# processor.net
KiCad netlist of a schematic drawn in Altium Designer
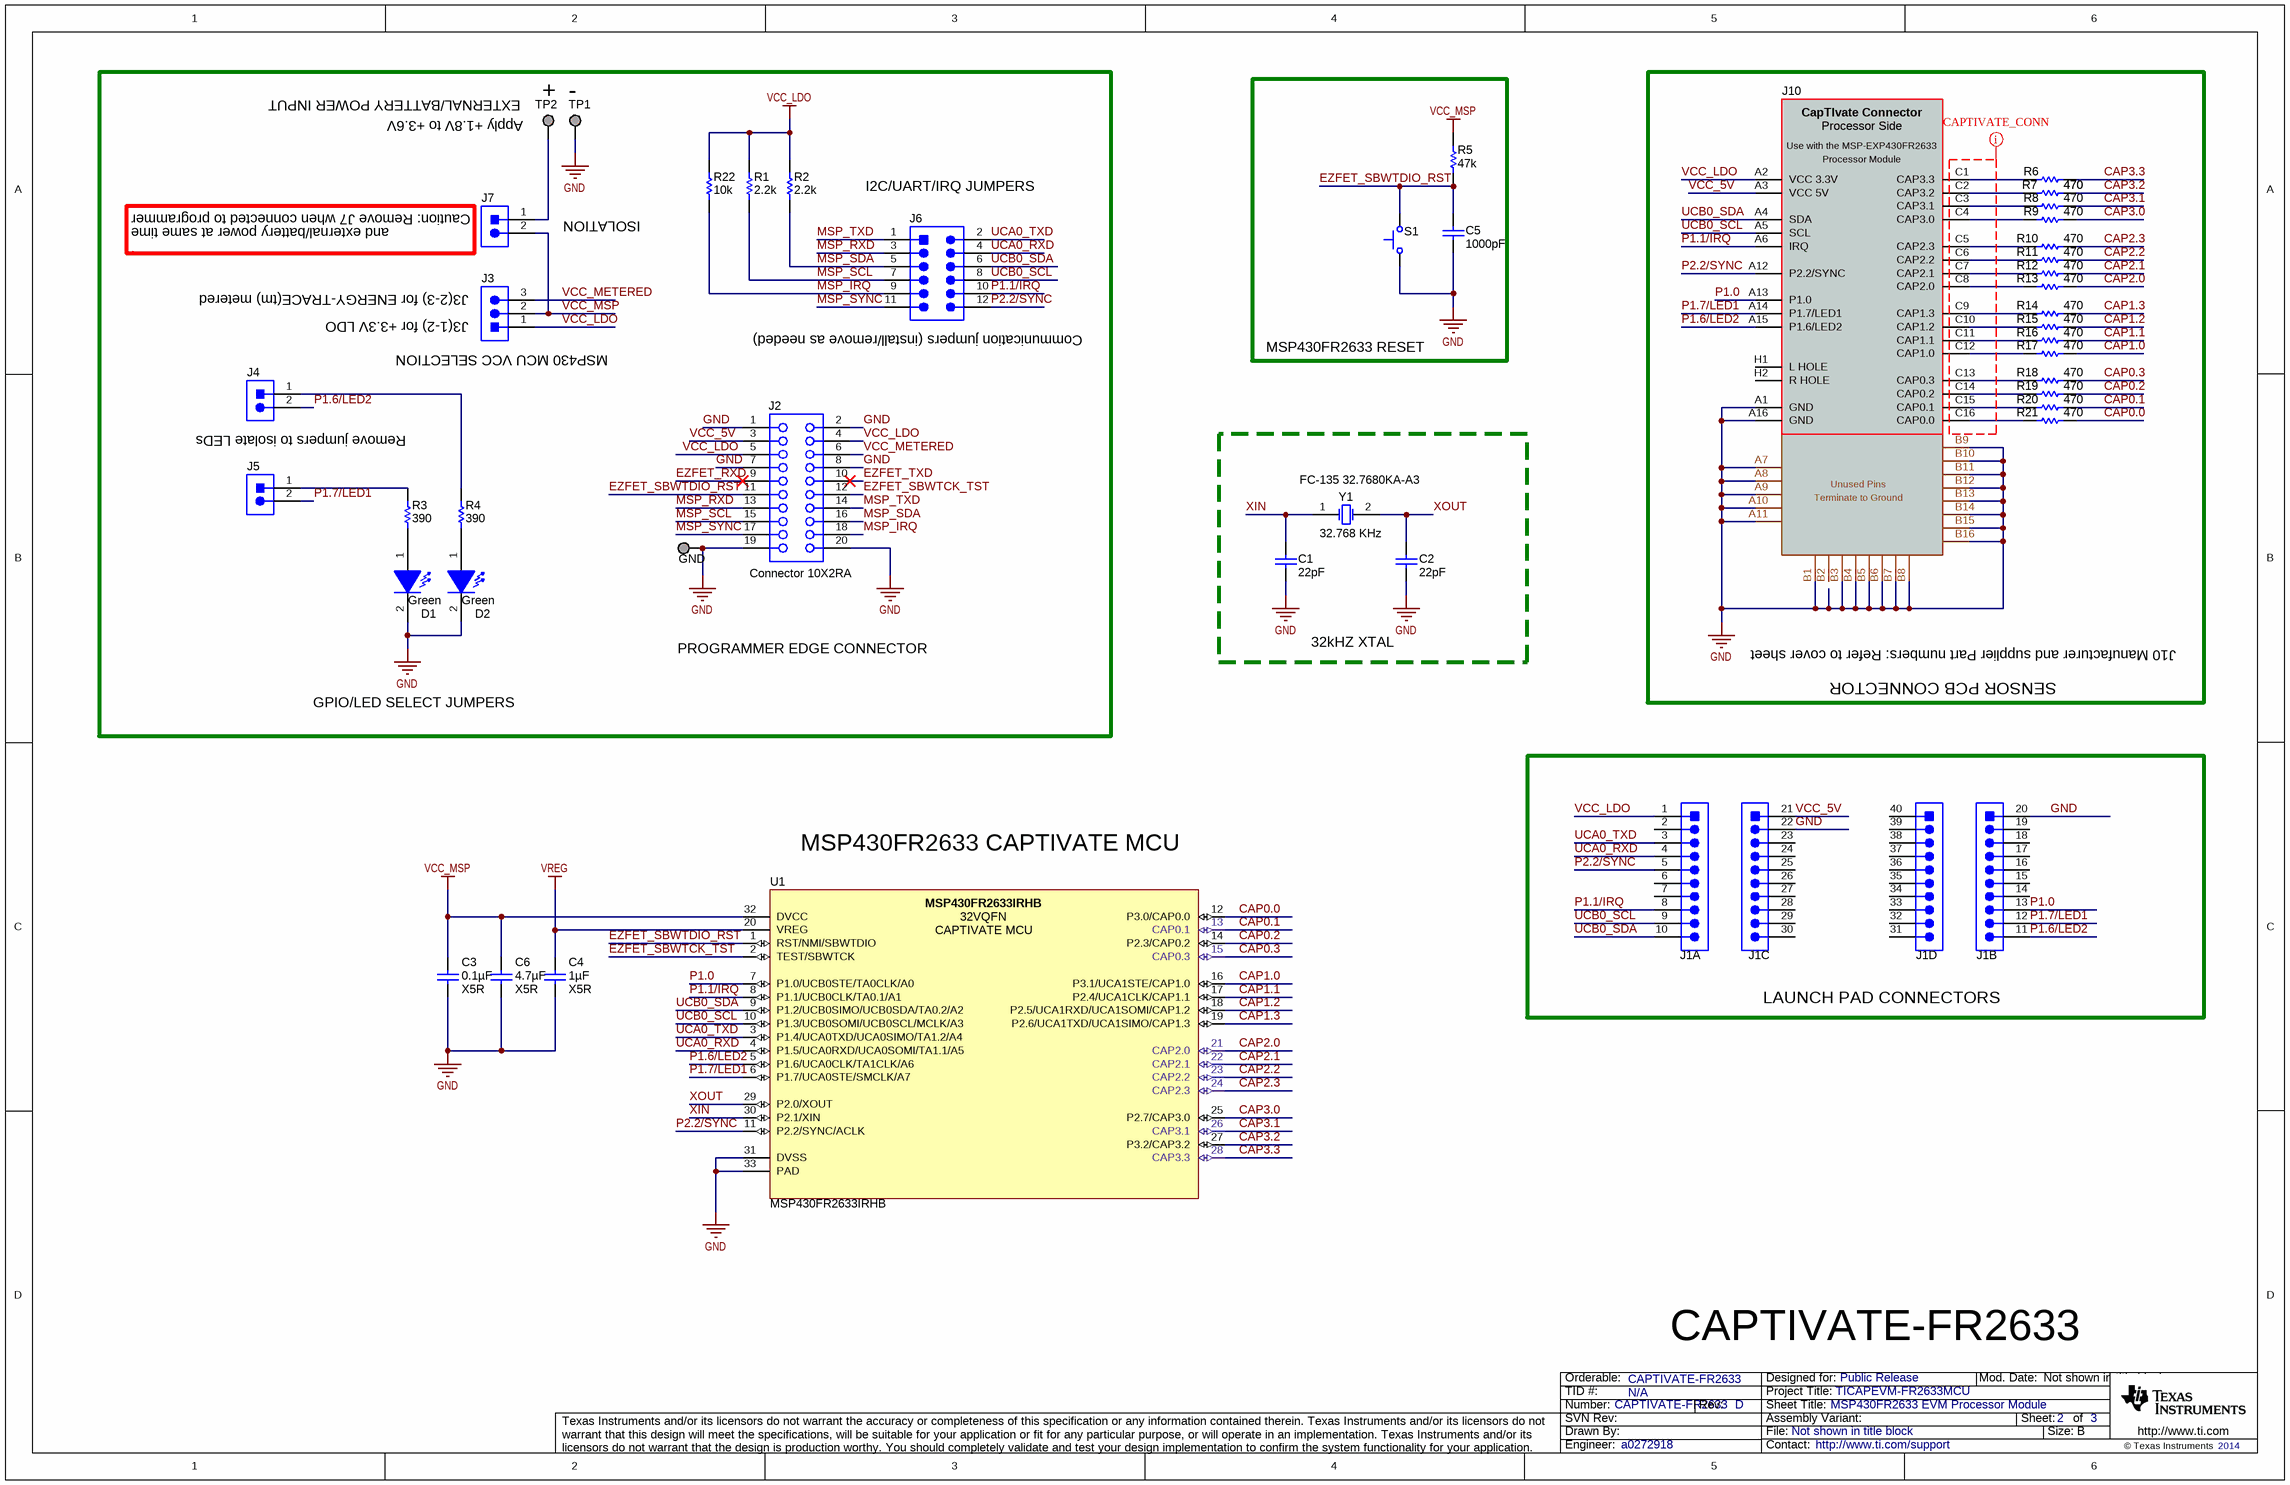
[diagram p0: processor.SchDoc]

(export (version "E")
  (design (tool "Eeschema 10.0.6"))
  (components
    (comp (ref "C1")
      (value "GRM1555C1H220JA01D")
      (footprint "0402")
      (description "CAP, CERM, 22 pF, 50 V, +/- 5%, C0G/NP0, 0402")
      (fields
        (field (name "VALUEDISPLAYED") "22pF")
        (field (name "MANUFACTURER") "MuRata")
        (field (name "PUBLISHER") "Texas Instruments")
      )
      (libsource (lib "Capacitor_Ceramic") (part "GRM1555C1H220JA01D"))
    )
    (comp (ref "C2")
      (value "GRM1555C1H220JA01D")
      (footprint "0402")
      (description "CAP, CERM, 22 pF, 50 V, +/- 5%, C0G/NP0, 0402")
      (fields
        (field (name "VALUEDISPLAYED") "22pF")
        (field (name "MANUFACTURER") "MuRata")
        (field (name "PUBLISHER") "Texas Instruments")
      )
      (libsource (lib "Capacitor_Ceramic") (part "GRM1555C1H220JA01D"))
    )
    (comp (ref "C3")
      (value "C1005X5R1A104K")
      (footprint "0402")
      (description "CAP, CERM, 0.1uF, 10V, +/-10%, X5R, 0402")
      (fields
        (field (name "VALUEDISPLAYED") "0.1µF")
        (field (name "MANUFACTURER") "TDK")
        (field (name "TEMPCO") "X5R")
        (field (name "PUBLISHER") "Texas Instruments")
      )
      (libsource (lib "Capacitor_Ceramic") (part "C1005X5R1A104K"))
    )
    (comp (ref "C4")
      (value "C1608X5R1A105K")
      (footprint "0603")
      (description "CAP, CERM, 1 µF, 10 V, +/- 10%, X5R, 0603")
      (fields
        (field (name "VALUEDISPLAYED") "1µF")
        (field (name "MANUFACTURER") "TDK")
        (field (name "TEMPCO") "X5R")
        (field (name "PUBLISHER") "Texas Instruments")
      )
      (libsource (lib "Capacitor_Ceramic") (part "C1608X5R1A105K"))
    )
    (comp (ref "C5")
      (value "C1005X7R1H102K")
      (footprint "0402")
      (description "CAP, CERM, 1000pF, 50V, +/-10%, X7R, 0402")
      (fields
        (field (name "VALUEDISPLAYED") "1000pF")
        (field (name "MANUFACTURER") "TDK")
        (field (name "PUBLISHER") "Texas Instruments")
      )
      (libsource (lib "Capacitor_Ceramic") (part "C1005X7R1H102K"))
    )
    (comp (ref "C6")
      (value "CGB3B1X5R1A475K055AC")
      (footprint "0603")
      (description "CAP, CERM, 4.7 µF, 10 V, +/- 10%, X5R, 0603")
      (fields
        (field (name "VALUEDISPLAYED") "4.7µF")
        (field (name "MANUFACTURER") "TDK")
        (field (name "TEMPCO") "X5R")
        (field (name "PUBLISHER") "Texas Instruments")
      )
      (libsource (lib "Capacitor_Ceramic") (part "CGB3B1X5R1A475K055AC"))
    )
    (comp (ref "D1")
      (value "Green")
      (footprint "LED_LTST-C190")
      (description "LED, Green, SMD")
      (fields
        (field (name "MANUFACTURER") "Lite-On")
        (field (name "PARTNUMBER") "LTST-C190GKT")
        (field (name "PUBLISHER") "Texas Instruments")
      )
      (libsource (lib "LED") (part "LTST-C190GKT"))
    )
    (comp (ref "D2")
      (value "Green")
      (footprint "LED_LTST-C190")
      (description "LED, Green, SMD")
      (fields
        (field (name "MANUFACTURER") "Lite-On")
        (field (name "PARTNUMBER") "LTST-C190GKT")
        (field (name "PUBLISHER") "Texas Instruments")
      )
      (libsource (lib "LED") (part "LTST-C190GKT"))
    )
    (comp (ref "GND")
      (value "TESTPOINT")
      (footprint "TP_VIA_060RND040")
      (description "TEST POINT.  No entry in BOM.")
      (fields (field (name "PUBLISHER") "Texas Instruments"))
      (libsource (lib "MiscParts") (part "TESTPOINT"))
    )
    (comp (ref "J1")
      (value "TSW-110-07-G-S")
      (footprint "40Pin BP")
      (description "Header, 100mil, 10x1, Gold, TH")
      (fields
        (field (name "MANUFACTURER") "Samtec")
        (field (name "SYMBOLCREATOR") "a0412235")
        (field (name "PUBLISHER") "Texas Instruments")
      )
      (libsource (lib "Captivate Library") (part "BoosterPack Connector"))
    )
    (comp (ref "J2")
      (value "Connector 10X2RA")
      (footprint "CONN2X10RA")
      (description "Connector, Female, 10-Pin, 2 row, Right Angle")
      (fields
        (field (name "MANUFACTURER") "Samtec")
        (field (name "PARTNUMBER") "SSW-110-22-F-D-RA")
        (field (name "PUBLISHER") "Altium Limited")
      )
      (libsource (lib "Captivate Library") (part "Connector 10X2RA"))
    )
    (comp (ref "J3")
      (value "HTSW-103-07-G-S")
      (footprint "Samtec_HTSW-103-07-G-S")
      (description "Header, 100mil, 3x1, Gold, TH")
      (fields
        (field (name "MANUFACTURER") "Samtec")
        (field (name "SYMBOLCREATOR") "a0799628")
        (field (name "PUBLISHER") "Texas Instruments")
      )
      (libsource (lib "Connectors_Samtec") (part "HTSW-103-07-G-S"))
    )
    (comp (ref "J4")
      (value "HTSW-102-07-G-S")
      (footprint "Samtec_HTSW-102-07-G-S")
      (description "Header, 100mil, 2x1, Gold, TH")
      (fields
        (field (name "MANUFACTURER") "Samtec")
        (field (name "SYMBOLCREATOR") "a0412235")
        (field (name "PUBLISHER") "Texas Instruments")
      )
      (libsource (lib "Connectors_Samtec") (part "HTSW-102-07-G-S"))
    )
    (comp (ref "J5")
      (value "HTSW-102-07-G-S")
      (footprint "Samtec_HTSW-102-07-G-S")
      (description "Header, 100mil, 2x1, Gold, TH")
      (fields
        (field (name "MANUFACTURER") "Samtec")
        (field (name "SYMBOLCREATOR") "a0412235")
        (field (name "PUBLISHER") "Texas Instruments")
      )
      (libsource (lib "Connectors_Samtec") (part "HTSW-102-07-G-S"))
    )
    (comp (ref "J6")
      (value "TSW-106-07-G-D")
      (footprint "TSW-106-07-G-D")
      (description "Header, 100mil, 6x2, Gold, TH")
      (fields
        (field (name "MANUFACTURER") "Samtec")
        (field (name "SYMBOLCREATOR") "a0412235")
        (field (name "PUBLISHER") "Texas Instruments")
      )
      (libsource (lib "Connectors") (part "TSW-106-07-G-D"))
    )
    (comp (ref "J7")
      (value "HTSW-102-07-G-S")
      (footprint "Samtec_HTSW-102-07-G-S")
      (description "Header, 100mil, 2x1, Gold, TH")
      (fields
        (field (name "MANUFACTURER") "Samtec")
        (field (name "SYMBOLCREATOR") "a0412235")
        (field (name "PUBLISHER") "Texas Instruments")
      )
      (libsource (lib "Connectors_Samtec") (part "HTSW-102-07-G-S"))
    )
    (comp (ref "J10")
      (value "09 28 248 6921")
      (footprint "CAPTIVATE-CONN-48-NONUM")
      (description "CapTIvate Processor-Side Connector, 3x16, 100mil, TH, RA, F, MSP-EXP430FR2633")
      (fields
        (field (name "MANUFACTURER") "Harting")
        (field (name "ALTERNATE PARTNUMBER") "5650868-4")
        (field (name "SYMBOLCREATOR") "Use a-id")
      )
      (libsource (lib "CapTIvate_Connector") (part "CAPTIVATE-CONN-MSP-EXP430FR2633-PROC"))
    )
    (comp (ref "R1")
      (value "CRCW04022K20JNED")
      (footprint "0402")
      (description "RES, 2.2 k, 5%, 0.063 W, 0402")
      (fields
        (field (name "MANUFACTURER") "Vishay-Dale")
        (field (name "VALUEDISPLAYED") "2.2k")
        (field (name "PUBLISHER") "Texas Instruments")
      )
      (libsource (lib "Resistor_0402") (part "CRCW04022K20JNED"))
    )
    (comp (ref "R2")
      (value "CRCW04022K20JNED")
      (footprint "0402")
      (description "RES, 2.2 k, 5%, 0.063 W, 0402")
      (fields
        (field (name "MANUFACTURER") "Vishay-Dale")
        (field (name "VALUEDISPLAYED") "2.2k")
        (field (name "PUBLISHER") "Texas Instruments")
      )
      (libsource (lib "Resistor_0402") (part "CRCW04022K20JNED"))
    )
    (comp (ref "R3")
      (value "390")
      (footprint "0402")
      (description "RES, 390 ohm, 5%, 0.063W, 0402")
      (fields
        (field (name "PARTNUMBER") "CRCW0402390RJNED")
        (field (name "MANUFACTURER") "Vishay-Dale")
        (field (name "PUBLISHER") "Texas Instruments")
      )
      (libsource (lib "Resistor_0402") (part "CRCW0402390RJNED"))
    )
    (comp (ref "R4")
      (value "390")
      (footprint "0402")
      (description "RES, 390 ohm, 5%, 0.063W, 0402")
      (fields
        (field (name "PARTNUMBER") "CRCW0402390RJNED")
        (field (name "MANUFACTURER") "Vishay-Dale")
        (field (name "PUBLISHER") "Texas Instruments")
      )
      (libsource (lib "Resistor_0402") (part "CRCW0402390RJNED"))
    )
    (comp (ref "R5")
      (value "47k")
      (footprint "0402")
      (description "RES, 47k ohm, 5%, 0.063W, 0402")
      (fields
        (field (name "PARTNUMBER") "CRCW040247K0JNED")
        (field (name "MANUFACTURER") "Vishay-Dale")
        (field (name "PUBLISHER") "Texas Instruments")
      )
      (libsource (lib "Resistor_0402") (part "CRCW040247K0JNED"))
    )
    (comp (ref "R6")
      (value "CRCW0402470RJNED")
      (footprint "0402")
      (description "RES, 470, 5%, 0.063 W, 0402")
      (fields
        (field (name "MANUFACTURER") "Vishay-Dale")
        (field (name "VALUEDISPLAYED") "470")
        (field (name "PUBLISHER") "Texas Instruments")
      )
      (libsource (lib "Resistor_0402") (part "CRCW0402470RJNED"))
    )
    (comp (ref "R7")
      (value "CRCW0402470RJNED")
      (footprint "0402")
      (description "RES, 470, 5%, 0.063 W, 0402")
      (fields
        (field (name "MANUFACTURER") "Vishay-Dale")
        (field (name "VALUEDISPLAYED") "470")
        (field (name "PUBLISHER") "Texas Instruments")
      )
      (libsource (lib "Resistor_0402") (part "CRCW0402470RJNED"))
    )
    (comp (ref "R8")
      (value "CRCW0402470RJNED")
      (footprint "0402")
      (description "RES, 470, 5%, 0.063 W, 0402")
      (fields
        (field (name "MANUFACTURER") "Vishay-Dale")
        (field (name "VALUEDISPLAYED") "470")
        (field (name "PUBLISHER") "Texas Instruments")
      )
      (libsource (lib "Resistor_0402") (part "CRCW0402470RJNED"))
    )
    (comp (ref "R9")
      (value "CRCW0402470RJNED")
      (footprint "0402")
      (description "RES, 470, 5%, 0.063 W, 0402")
      (fields
        (field (name "MANUFACTURER") "Vishay-Dale")
        (field (name "VALUEDISPLAYED") "470")
        (field (name "PUBLISHER") "Texas Instruments")
      )
      (libsource (lib "Resistor_0402") (part "CRCW0402470RJNED"))
    )
    (comp (ref "R10")
      (value "CRCW0402470RJNED")
      (footprint "0402")
      (description "RES, 470, 5%, 0.063 W, 0402")
      (fields
        (field (name "MANUFACTURER") "Vishay-Dale")
        (field (name "VALUEDISPLAYED") "470")
        (field (name "PUBLISHER") "Texas Instruments")
      )
      (libsource (lib "Resistor_0402") (part "CRCW0402470RJNED"))
    )
    (comp (ref "R11")
      (value "CRCW0402470RJNED")
      (footprint "0402")
      (description "RES, 470, 5%, 0.063 W, 0402")
      (fields
        (field (name "MANUFACTURER") "Vishay-Dale")
        (field (name "VALUEDISPLAYED") "470")
        (field (name "PUBLISHER") "Texas Instruments")
      )
      (libsource (lib "Resistor_0402") (part "CRCW0402470RJNED"))
    )
    (comp (ref "R12")
      (value "CRCW0402470RJNED")
      (footprint "0402")
      (description "RES, 470, 5%, 0.063 W, 0402")
      (fields
        (field (name "MANUFACTURER") "Vishay-Dale")
        (field (name "VALUEDISPLAYED") "470")
        (field (name "PUBLISHER") "Texas Instruments")
      )
      (libsource (lib "Resistor_0402") (part "CRCW0402470RJNED"))
    )
    (comp (ref "R13")
      (value "CRCW0402470RJNED")
      (footprint "0402")
      (description "RES, 470, 5%, 0.063 W, 0402")
      (fields
        (field (name "MANUFACTURER") "Vishay-Dale")
        (field (name "VALUEDISPLAYED") "470")
        (field (name "PUBLISHER") "Texas Instruments")
      )
      (libsource (lib "Resistor_0402") (part "CRCW0402470RJNED"))
    )
    (comp (ref "R14")
      (value "CRCW0402470RJNED")
      (footprint "0402")
      (description "RES, 470, 5%, 0.063 W, 0402")
      (fields
        (field (name "MANUFACTURER") "Vishay-Dale")
        (field (name "VALUEDISPLAYED") "470")
        (field (name "PUBLISHER") "Texas Instruments")
      )
      (libsource (lib "Resistor_0402") (part "CRCW0402470RJNED"))
    )
    (comp (ref "R15")
      (value "CRCW0402470RJNED")
      (footprint "0402")
      (description "RES, 470, 5%, 0.063 W, 0402")
      (fields
        (field (name "MANUFACTURER") "Vishay-Dale")
        (field (name "VALUEDISPLAYED") "470")
        (field (name "PUBLISHER") "Texas Instruments")
      )
      (libsource (lib "Resistor_0402") (part "CRCW0402470RJNED"))
    )
    (comp (ref "R16")
      (value "CRCW0402470RJNED")
      (footprint "0402")
      (description "RES, 470, 5%, 0.063 W, 0402")
      (fields
        (field (name "MANUFACTURER") "Vishay-Dale")
        (field (name "VALUEDISPLAYED") "470")
        (field (name "PUBLISHER") "Texas Instruments")
      )
      (libsource (lib "Resistor_0402") (part "CRCW0402470RJNED"))
    )
    (comp (ref "R17")
      (value "CRCW0402470RJNED")
      (footprint "0402")
      (description "RES, 470, 5%, 0.063 W, 0402")
      (fields
        (field (name "MANUFACTURER") "Vishay-Dale")
        (field (name "VALUEDISPLAYED") "470")
        (field (name "PUBLISHER") "Texas Instruments")
      )
      (libsource (lib "Resistor_0402") (part "CRCW0402470RJNED"))
    )
    (comp (ref "R18")
      (value "CRCW0402470RJNED")
      (footprint "0402")
      (description "RES, 470, 5%, 0.063 W, 0402")
      (fields
        (field (name "MANUFACTURER") "Vishay-Dale")
        (field (name "VALUEDISPLAYED") "470")
        (field (name "PUBLISHER") "Texas Instruments")
      )
      (libsource (lib "Resistor_0402") (part "CRCW0402470RJNED"))
    )
    (comp (ref "R19")
      (value "CRCW0402470RJNED")
      (footprint "0402")
      (description "RES, 470, 5%, 0.063 W, 0402")
      (fields
        (field (name "MANUFACTURER") "Vishay-Dale")
        (field (name "VALUEDISPLAYED") "470")
        (field (name "PUBLISHER") "Texas Instruments")
      )
      (libsource (lib "Resistor_0402") (part "CRCW0402470RJNED"))
    )
    (comp (ref "R20")
      (value "CRCW0402470RJNED")
      (footprint "0402")
      (description "RES, 470, 5%, 0.063 W, 0402")
      (fields
        (field (name "MANUFACTURER") "Vishay-Dale")
        (field (name "VALUEDISPLAYED") "470")
        (field (name "PUBLISHER") "Texas Instruments")
      )
      (libsource (lib "Resistor_0402") (part "CRCW0402470RJNED"))
    )
    (comp (ref "R21")
      (value "CRCW0402470RJNED")
      (footprint "0402")
      (description "RES, 470, 5%, 0.063 W, 0402")
      (fields
        (field (name "MANUFACTURER") "Vishay-Dale")
        (field (name "VALUEDISPLAYED") "470")
        (field (name "PUBLISHER") "Texas Instruments")
      )
      (libsource (lib "Resistor_0402") (part "CRCW0402470RJNED"))
    )
    (comp (ref "R22")
      (value "CRCW040210K0JNED")
      (footprint "0402")
      (description "RES, 10 k, 5%, 0.063 W, 0402")
      (fields
        (field (name "MANUFACTURER") "Vishay-Dale")
        (field (name "VALUEDISPLAYED") "10k")
        (field (name "PUBLISHER") "Texas Instruments")
      )
      (libsource (lib "Resistor_0402") (part "CRCW040210K0JNED"))
    )
    (comp (ref "S1")
      (value "EVQ-21505R")
      (footprint "SW_EVQ-21x05")
      (description "Switch, Tactile, SPST-NO, 0.02A, 15V, TH")
      (fields (field (name "MANUFACTURER") "Panasonic") (field (name "PUBLISHER") "Texas Instruments"))
      (libsource (lib "Switches") (part "EVQ-21505R"))
    )
    (comp (ref "TP1")
      (value "-")
      (footprint "TESTPOINT")
      (description "TEST POINT.  No entry in BOM.")
      (fields (field (name "PUBLISHER") "Texas Instruments"))
      (libsource (lib "MiscParts") (part "TESTPOINT"))
    )
    (comp (ref "TP2")
      (value "+")
      (footprint "TESTPOINT")
      (description "TEST POINT.  No entry in BOM.")
      (fields (field (name "PUBLISHER") "Texas Instruments"))
      (libsource (lib "MiscParts") (part "TESTPOINT"))
    )
    (comp (ref "U1")
      (value "MSP430FR2633IRHB")
      (footprint "RHB0032E")
      (description "MSP430 Captivate Microcontroller")
      (fields (field (name "MANUFACTURER") "Texas Instruments") (field (name "SYMBOLCREATOR") "W. Schnoor"))
      (libsource (lib "Captivate Library") (part "MSP430FR2633IRHB"))
    )
    (comp (ref "Y1")
      (value "FC-135 32.7680KA-A3")
      (footprint "Epson_FC-135")
      (description "Crystal, 32.768 KHz, 12.5 pF, SMD")
      (fields
        (field (name "FREQUENCY") "32.768 KHz")
        (field (name "MANUFACTURER") "Epson")
        (field (name "SYMBOLCREATOR") "a0412235")
        (field (name "PUBLISHER") "Texas Instruments")
      )
      (libsource (lib "Oscillators") (part "FC-135 32.7680KA-A3"))
    )
  )
  (nets
    (net (code "1") (name "/CAP0.0") (class "Default")
      (node (ref "R21") (pin "2") (pinfunction "2_2") (pintype "passive"))
      (node (ref "U1") (pin "12") (pinfunction "P3.0/CAP0.0_12") (pintype "bidirectional"))
    )
    (net (code "2") (name "/CAP0.1") (class "Default")
      (node (ref "R20") (pin "2") (pinfunction "2_2") (pintype "passive"))
      (node (ref "U1") (pin "13") (pinfunction "CAP0.1_13") (pintype "bidirectional"))
    )
    (net (code "3") (name "/CAP0.2") (class "Default")
      (node (ref "R19") (pin "2") (pinfunction "2_2") (pintype "passive"))
      (node (ref "U1") (pin "14") (pinfunction "P2.3/CAP0.2_14") (pintype "bidirectional"))
    )
    (net (code "4") (name "/CAP0.3") (class "Default")
      (node (ref "R18") (pin "2") (pinfunction "2_2") (pintype "passive"))
      (node (ref "U1") (pin "15") (pinfunction "CAP0.3_15") (pintype "bidirectional"))
    )
    (net (code "5") (name "/CAP1.0") (class "Default")
      (node (ref "R17") (pin "2") (pinfunction "2_2") (pintype "passive"))
      (node (ref "U1") (pin "16") (pinfunction "P3.1/UCA1STE/CAP1.0_16") (pintype "bidirectional"))
    )
    (net (code "6") (name "/CAP1.1") (class "Default")
      (node (ref "R16") (pin "2") (pinfunction "2_2") (pintype "passive"))
      (node (ref "U1") (pin "17") (pinfunction "P2.4/UCA1CLK/CAP1.1_17") (pintype "bidirectional"))
    )
    (net (code "7") (name "/CAP1.2") (class "Default")
      (node (ref "R15") (pin "2") (pinfunction "2_2") (pintype "passive"))
      (node (ref "U1") (pin "18") (pinfunction "P2.5/UCA1RXD/UCA1SOMI/CAP1.2_18") (pintype "bidirectional"))
    )
    (net (code "8") (name "/CAP1.3") (class "Default")
      (node (ref "R14") (pin "2") (pinfunction "2_2") (pintype "passive"))
      (node (ref "U1") (pin "19") (pinfunction "P2.6/UCA1TXD/UCA1SIMO/CAP1.3_19") (pintype "bidirectional"))
    )
    (net (code "9") (name "/CAP2.0") (class "Default")
      (node (ref "R13") (pin "2") (pinfunction "2_2") (pintype "passive"))
      (node (ref "U1") (pin "21") (pinfunction "CAP2.0_21") (pintype "bidirectional"))
    )
    (net (code "10") (name "/CAP2.1") (class "Default")
      (node (ref "R12") (pin "2") (pinfunction "2_2") (pintype "passive"))
      (node (ref "U1") (pin "22") (pinfunction "CAP2.1_22") (pintype "bidirectional"))
    )
    (net (code "11") (name "/CAP2.2") (class "Default")
      (node (ref "R11") (pin "2") (pinfunction "2_2") (pintype "passive"))
      (node (ref "U1") (pin "23") (pinfunction "CAP2.2_23") (pintype "bidirectional"))
    )
    (net (code "12") (name "/CAP2.3") (class "Default")
      (node (ref "R10") (pin "2") (pinfunction "2_2") (pintype "passive"))
      (node (ref "U1") (pin "24") (pinfunction "CAP2.3_24") (pintype "bidirectional"))
    )
    (net (code "13") (name "/CAP3.0") (class "Default")
      (node (ref "R9") (pin "2") (pinfunction "2_2") (pintype "passive"))
      (node (ref "U1") (pin "25") (pinfunction "P2.7/CAP3.0_25") (pintype "bidirectional"))
    )
    (net (code "14") (name "/CAP3.1") (class "Default")
      (node (ref "R8") (pin "2") (pinfunction "2_2") (pintype "passive"))
      (node (ref "U1") (pin "26") (pinfunction "CAP3.1_26") (pintype "bidirectional"))
    )
    (net (code "15") (name "/CAP3.2") (class "Default")
      (node (ref "R7") (pin "2") (pinfunction "2_2") (pintype "passive"))
      (node (ref "U1") (pin "27") (pinfunction "P3.2/CAP3.2_27") (pintype "bidirectional"))
    )
    (net (code "16") (name "/CAP3.3") (class "Default")
      (node (ref "R6") (pin "2") (pinfunction "2_2") (pintype "passive"))
      (node (ref "U1") (pin "28") (pinfunction "CAP3.3_28") (pintype "bidirectional"))
    )
    (net (code "17") (name "/EZFET_RXD") (class "Default")
      (node (ref "J2") (pin "9") (pinfunction "9_9") (pintype "passive+no_connect"))
    )
    (net (code "18") (name "/EZFET_SBWTCK_TST") (class "Default")
      (node (ref "J2") (pin "12") (pinfunction "12_12") (pintype "passive"))
      (node (ref "U1") (pin "2") (pinfunction "TEST/SBWTCK_2") (pintype "bidirectional"))
    )
    (net (code "19") (name "/EZFET_SBWTDIO_RST") (class "Default")
      (node (ref "C5") (pin "1") (pinfunction "1_1") (pintype "passive"))
      (node (ref "J2") (pin "11") (pinfunction "11_11") (pintype "passive"))
      (node (ref "R5") (pin "1") (pinfunction "1_1") (pintype "passive"))
      (node (ref "S1") (pin "2") (pinfunction "2_2") (pintype "passive"))
      (node (ref "U1") (pin "1") (pinfunction "RST/NMI/SBWTDIO_1") (pintype "bidirectional"))
    )
    (net (code "20") (name "/EZFET_TXD") (class "Default")
      (node (ref "J2") (pin "10") (pinfunction "10_10") (pintype "passive+no_connect"))
    )
    (net (code "21") (name "/MSP_IRQ") (class "Default")
      (node (ref "J2") (pin "18") (pinfunction "18_18") (pintype "passive"))
      (node (ref "J6") (pin "9") (pinfunction "9_9") (pintype "passive"))
      (node (ref "R22") (pin "1") (pinfunction "1_1") (pintype "passive"))
    )
    (net (code "22") (name "/MSP_RXD") (class "Default")
      (node (ref "J2") (pin "13") (pinfunction "13_13") (pintype "passive"))
      (node (ref "J6") (pin "3") (pinfunction "3_3") (pintype "passive"))
    )
    (net (code "23") (name "/MSP_SCL") (class "Default")
      (node (ref "J2") (pin "15") (pinfunction "15_15") (pintype "passive"))
      (node (ref "J6") (pin "7") (pinfunction "7_7") (pintype "passive"))
      (node (ref "R1") (pin "1") (pinfunction "1_1") (pintype "passive"))
    )
    (net (code "24") (name "/MSP_SDA") (class "Default")
      (node (ref "J2") (pin "16") (pinfunction "16_16") (pintype "passive"))
      (node (ref "J6") (pin "5") (pinfunction "5_5") (pintype "passive"))
      (node (ref "R2") (pin "1") (pinfunction "1_1") (pintype "passive"))
    )
    (net (code "25") (name "/MSP_SYNC") (class "Default")
      (node (ref "J2") (pin "17") (pinfunction "17_17") (pintype "passive"))
      (node (ref "J6") (pin "11") (pinfunction "11_11") (pintype "passive"))
    )
    (net (code "26") (name "/MSP_TXD") (class "Default")
      (node (ref "J2") (pin "14") (pinfunction "14_14") (pintype "passive"))
      (node (ref "J6") (pin "1") (pinfunction "1_1") (pintype "passive"))
    )
    (net (code "27") (name "/P1.0") (class "Default")
      (node (ref "J1") (pin "13") (pinfunction "13_13") (pintype "passive"))
      (node (ref "J10") (pin "A13") (pinfunction "P1.0_A13") (pintype "open_collector"))
      (node (ref "U1") (pin "7") (pinfunction "P1.0/UCB0STE/TA0CLK/A0_7") (pintype "bidirectional"))
    )
    (net (code "28") (name "/P1.1{slash}IRQ") (class "Default")
      (node (ref "J1") (pin "8") (pinfunction "8_8") (pintype "passive"))
      (node (ref "J10") (pin "A6") (pinfunction "IRQ_A6") (pintype "open_collector"))
      (node (ref "J6") (pin "10") (pinfunction "10_10") (pintype "passive"))
      (node (ref "U1") (pin "8") (pinfunction "P1.1/UCB0CLK/TA0.1/A1_8") (pintype "bidirectional"))
    )
    (net (code "29") (name "/P1.6{slash}LED2") (class "Default")
      (node (ref "J1") (pin "11") (pinfunction "11_11") (pintype "passive"))
      (node (ref "J10") (pin "A15") (pinfunction "P1.6/LED2_A15") (pintype "open_collector"))
      (node (ref "J4") (pin "2") (pinfunction "2_2") (pintype "passive"))
      (node (ref "U1") (pin "5") (pinfunction "P1.6/UCA0CLK/TA1CLK/A6_5") (pintype "bidirectional"))
    )
    (net (code "30") (name "/P1.7{slash}LED1") (class "Default")
      (node (ref "J1") (pin "12") (pinfunction "12_12") (pintype "passive"))
      (node (ref "J10") (pin "A14") (pinfunction "P1.7/LED1_A14") (pintype "open_collector"))
      (node (ref "J5") (pin "2") (pinfunction "2_2") (pintype "passive"))
      (node (ref "U1") (pin "6") (pinfunction "P1.7/UCA0STE/SMCLK/A7_6") (pintype "bidirectional"))
    )
    (net (code "31") (name "/P2.2{slash}SYNC") (class "Default")
      (node (ref "J1") (pin "5") (pinfunction "5_5") (pintype "passive"))
      (node (ref "J10") (pin "A12") (pinfunction "P2.2/SYNC_A12") (pintype "open_collector"))
      (node (ref "J6") (pin "12") (pinfunction "12_12") (pintype "passive"))
      (node (ref "U1") (pin "11") (pinfunction "P2.2/SYNC/ACLK_11") (pintype "bidirectional"))
    )
    (net (code "32") (name "/UCA0_RXD") (class "Default")
      (node (ref "J1") (pin "4") (pinfunction "4_4") (pintype "passive"))
      (node (ref "J6") (pin "4") (pinfunction "4_4") (pintype "passive"))
      (node (ref "U1") (pin "4") (pinfunction "P1.5/UCA0RXD/UCA0SOMI/TA1.1/A5_4") (pintype "bidirectional"))
    )
    (net (code "33") (name "/UCA0_TXD") (class "Default")
      (node (ref "J1") (pin "3") (pinfunction "3_3") (pintype "passive"))
      (node (ref "J6") (pin "2") (pinfunction "2_2") (pintype "passive"))
      (node (ref "U1") (pin "3") (pinfunction "P1.4/UCA0TXD/UCA0SIMO/TA1.2/A4_3") (pintype "bidirectional"))
    )
    (net (code "34") (name "/UCB0_SCL") (class "Default")
      (node (ref "J1") (pin "9") (pinfunction "9_9") (pintype "passive"))
      (node (ref "J10") (pin "A5") (pinfunction "SCL_A5") (pintype "open_collector"))
      (node (ref "J6") (pin "8") (pinfunction "8_8") (pintype "passive"))
      (node (ref "U1") (pin "10") (pinfunction "P1.3/UCB0SOMI/UCB0SCL/MCLK/A3_10") (pintype "bidirectional"))
    )
    (net (code "35") (name "/UCB0_SDA") (class "Default")
      (node (ref "J1") (pin "10") (pinfunction "10_10") (pintype "passive"))
      (node (ref "J10") (pin "A4") (pinfunction "SDA_A4") (pintype "open_collector"))
      (node (ref "J6") (pin "6") (pinfunction "6_6") (pintype "passive"))
      (node (ref "U1") (pin "9") (pinfunction "P1.2/UCB0SIMO/UCB0SDA/TA0.2/A2_9") (pintype "bidirectional"))
    )
    (net (code "36") (name "/VCC_5V") (class "Default")
      (node (ref "J1") (pin "21") (pinfunction "21_21") (pintype "passive"))
      (node (ref "J10") (pin "A3") (pinfunction "VCC_5V_A3") (pintype "power_in"))
      (node (ref "J2") (pin "3") (pinfunction "3_3") (pintype "passive"))
    )
    (net (code "37") (name "/VCC_METERED") (class "Default")
      (node (ref "J2") (pin "6") (pinfunction "6_6") (pintype "passive"))
      (node (ref "J3") (pin "3") (pinfunction "3_3") (pintype "passive"))
    )
    (net (code "38") (name "/XIN") (class "Default")
      (node (ref "C1") (pin "1") (pinfunction "1_1") (pintype "passive"))
      (node (ref "U1") (pin "30") (pinfunction "P2.1/XIN_30") (pintype "bidirectional"))
      (node (ref "Y1") (pin "1") (pinfunction "OSC1_1") (pintype "passive"))
    )
    (net (code "39") (name "/XOUT") (class "Default")
      (node (ref "C2") (pin "1") (pinfunction "1_1") (pintype "passive"))
      (node (ref "U1") (pin "29") (pinfunction "P2.0/XOUT_29") (pintype "bidirectional"))
      (node (ref "Y1") (pin "2") (pinfunction "OSC2_2") (pintype "passive"))
    )
    (net (code "40") (name "GND") (class "Default")
      (node (ref "C1") (pin "2") (pinfunction "2_2") (pintype "passive"))
      (node (ref "C2") (pin "2") (pinfunction "2_2") (pintype "passive"))
      (node (ref "C3") (pin "2") (pinfunction "2_2") (pintype "passive"))
      (node (ref "C4") (pin "2") (pinfunction "2_2") (pintype "passive"))
      (node (ref "C5") (pin "2") (pinfunction "2_2") (pintype "passive"))
      (node (ref "C6") (pin "2") (pinfunction "2_2") (pintype "passive"))
      (node (ref "D1") (pin "2") (pinfunction "K_2") (pintype "passive"))
      (node (ref "D2") (pin "2") (pinfunction "K_2") (pintype "passive"))
      (node (ref "GND") (pin "1") (pintype "passive"))
      (node (ref "J1") (pin "20") (pinfunction "20_20") (pintype "passive"))
      (node (ref "J1") (pin "22") (pinfunction "22_22") (pintype "passive"))
      (node (ref "J10") (pin "A1") (pinfunction "GND_A1") (pintype "power_in"))
      (node (ref "J10") (pin "A10") (pinfunction "A10_A10") (pintype "passive"))
      (node (ref "J10") (pin "A11") (pinfunction "A11_A11") (pintype "passive"))
      (node (ref "J10") (pin "A16") (pinfunction "GND_A16") (pintype "power_in"))
      (node (ref "J10") (pin "A7") (pinfunction "A7_A7") (pintype "passive"))
      (node (ref "J10") (pin "A8") (pinfunction "A8_A8") (pintype "passive"))
      (node (ref "J10") (pin "A9") (pinfunction "A9_A9") (pintype "passive"))
      (node (ref "J10") (pin "B1") (pinfunction "B1_B1") (pintype "passive"))
      (node (ref "J10") (pin "B10") (pinfunction "B10_B10") (pintype "passive"))
      (node (ref "J10") (pin "B11") (pinfunction "B11_B11") (pintype "passive"))
      (node (ref "J10") (pin "B12") (pinfunction "B12_B12") (pintype "passive"))
      (node (ref "J10") (pin "B13") (pinfunction "B13_B13") (pintype "passive"))
      (node (ref "J10") (pin "B14") (pinfunction "B14_B14") (pintype "passive"))
      (node (ref "J10") (pin "B15") (pinfunction "B15_B15") (pintype "passive"))
      (node (ref "J10") (pin "B16") (pinfunction "B16_B16") (pintype "passive"))
      (node (ref "J10") (pin "B3") (pinfunction "B3_B3") (pintype "passive"))
      (node (ref "J10") (pin "B4") (pinfunction "B4_B4") (pintype "passive"))
      (node (ref "J10") (pin "B5") (pinfunction "B5_B5") (pintype "passive"))
      (node (ref "J10") (pin "B6") (pinfunction "B6_B6") (pintype "passive"))
      (node (ref "J10") (pin "B7") (pinfunction "B7_B7") (pintype "passive"))
      (node (ref "J10") (pin "B8") (pinfunction "B8_B8") (pintype "passive"))
      (node (ref "J10") (pin "B9") (pinfunction "B9_B9") (pintype "passive"))
      (node (ref "J2") (pin "1") (pinfunction "1_1") (pintype "passive"))
      (node (ref "J2") (pin "19") (pinfunction "19_19") (pintype "passive"))
      (node (ref "J2") (pin "2") (pinfunction "2_2") (pintype "passive"))
      (node (ref "J2") (pin "20") (pinfunction "20_20") (pintype "passive"))
      (node (ref "J2") (pin "7") (pinfunction "7_7") (pintype "passive"))
      (node (ref "J2") (pin "8") (pinfunction "8_8") (pintype "passive"))
      (node (ref "S1") (pin "1") (pinfunction "1_1") (pintype "passive"))
      (node (ref "TP1") (pin "1") (pintype "passive"))
      (node (ref "U1") (pin "31") (pinfunction "DVSS_31") (pintype "power_in"))
      (node (ref "U1") (pin "33") (pinfunction "PAD_33") (pintype "power_in"))
    )
    (net (code "41") (name "Net-(D1-A)") (class "Default")
      (node (ref "D1") (pin "1") (pinfunction "A_1") (pintype "passive"))
      (node (ref "R3") (pin "1") (pinfunction "1_1") (pintype "passive"))
    )
    (net (code "42") (name "Net-(D2-A)") (class "Default")
      (node (ref "D2") (pin "1") (pinfunction "A_1") (pintype "passive"))
      (node (ref "R4") (pin "1") (pinfunction "1_1") (pintype "passive"))
    )
    (net (code "43") (name "Net-(J4-Pad1)") (class "Default")
      (node (ref "J4") (pin "1") (pinfunction "1_1") (pintype "passive"))
      (node (ref "R4") (pin "2") (pinfunction "2_2") (pintype "passive"))
    )
    (net (code "44") (name "Net-(J5-Pad1)") (class "Default")
      (node (ref "J5") (pin "1") (pinfunction "1_1") (pintype "passive"))
      (node (ref "R3") (pin "2") (pinfunction "2_2") (pintype "passive"))
    )
    (net (code "45") (name "Net-(J7-Pad1)") (class "Default")
      (node (ref "J7") (pin "1") (pinfunction "1_1") (pintype "passive"))
      (node (ref "TP2") (pin "1") (pintype "passive"))
    )
    (net (code "46") (name "Net-(J10-CAP0.0)") (class "Default")
      (node (ref "J10") (pin "C16") (pinfunction "CAP0.0_C16") (pintype "passive"))
      (node (ref "R21") (pin "1") (pinfunction "1_1") (pintype "passive"))
    )
    (net (code "47") (name "Net-(J10-CAP0.1)") (class "Default")
      (node (ref "J10") (pin "C15") (pinfunction "CAP0.1_C15") (pintype "passive"))
      (node (ref "R20") (pin "1") (pinfunction "1_1") (pintype "passive"))
    )
    (net (code "48") (name "Net-(J10-CAP0.2)") (class "Default")
      (node (ref "J10") (pin "C14") (pinfunction "CAP0.2_C14") (pintype "passive"))
      (node (ref "R19") (pin "1") (pinfunction "1_1") (pintype "passive"))
    )
    (net (code "49") (name "Net-(J10-CAP0.3)") (class "Default")
      (node (ref "J10") (pin "C13") (pinfunction "CAP0.3_C13") (pintype "passive"))
      (node (ref "R18") (pin "1") (pinfunction "1_1") (pintype "passive"))
    )
    (net (code "50") (name "Net-(J10-CAP1.0)") (class "Default")
      (node (ref "J10") (pin "C12") (pinfunction "CAP1.0_C12") (pintype "passive"))
      (node (ref "R17") (pin "1") (pinfunction "1_1") (pintype "passive"))
    )
    (net (code "51") (name "Net-(J10-CAP1.1)") (class "Default")
      (node (ref "J10") (pin "C11") (pinfunction "CAP1.1_C11") (pintype "passive"))
      (node (ref "R16") (pin "1") (pinfunction "1_1") (pintype "passive"))
    )
    (net (code "52") (name "Net-(J10-CAP1.2)") (class "Default")
      (node (ref "J10") (pin "C10") (pinfunction "CAP1.2_C10") (pintype "passive"))
      (node (ref "R15") (pin "1") (pinfunction "1_1") (pintype "passive"))
    )
    (net (code "53") (name "Net-(J10-CAP1.3)") (class "Default")
      (node (ref "J10") (pin "C9") (pinfunction "CAP1.3_C9") (pintype "passive"))
      (node (ref "R14") (pin "1") (pinfunction "1_1") (pintype "passive"))
    )
    (net (code "54") (name "Net-(J10-CAP2.0)") (class "Default")
      (node (ref "J10") (pin "C8") (pinfunction "CAP2.0_C8") (pintype "passive"))
      (node (ref "R13") (pin "1") (pinfunction "1_1") (pintype "passive"))
    )
    (net (code "55") (name "Net-(J10-CAP2.1)") (class "Default")
      (node (ref "J10") (pin "C7") (pinfunction "CAP2.1_C7") (pintype "passive"))
      (node (ref "R12") (pin "1") (pinfunction "1_1") (pintype "passive"))
    )
    (net (code "56") (name "Net-(J10-CAP2.2)") (class "Default")
      (node (ref "J10") (pin "C6") (pinfunction "CAP2.2_C6") (pintype "passive"))
      (node (ref "R11") (pin "1") (pinfunction "1_1") (pintype "passive"))
    )
    (net (code "57") (name "Net-(J10-CAP2.3)") (class "Default")
      (node (ref "J10") (pin "C5") (pinfunction "CAP2.3_C5") (pintype "passive"))
      (node (ref "R10") (pin "1") (pinfunction "1_1") (pintype "passive"))
    )
    (net (code "58") (name "Net-(J10-CAP3.0)") (class "Default")
      (node (ref "J10") (pin "C4") (pinfunction "CAP3.0_C4") (pintype "passive"))
      (node (ref "R9") (pin "1") (pinfunction "1_1") (pintype "passive"))
    )
    (net (code "59") (name "Net-(J10-CAP3.1)") (class "Default")
      (node (ref "J10") (pin "C3") (pinfunction "CAP3.1_C3") (pintype "passive"))
      (node (ref "R8") (pin "1") (pinfunction "1_1") (pintype "passive"))
    )
    (net (code "60") (name "Net-(J10-CAP3.2)") (class "Default")
      (node (ref "J10") (pin "C2") (pinfunction "CAP3.2_C2") (pintype "passive"))
      (node (ref "R7") (pin "1") (pinfunction "1_1") (pintype "passive"))
    )
    (net (code "61") (name "Net-(J10-CAP3.3)") (class "Default")
      (node (ref "J10") (pin "C1") (pinfunction "CAP3.3_C1") (pintype "passive"))
      (node (ref "R6") (pin "1") (pinfunction "1_1") (pintype "passive"))
    )
    (net (code "62") (name "VCC_LDO") (class "Default")
      (node (ref "J1") (pin "1") (pinfunction "1_1") (pintype "passive"))
      (node (ref "J10") (pin "A2") (pinfunction "VCC_3.3V_A2") (pintype "power_in"))
      (node (ref "J2") (pin "4") (pinfunction "4_4") (pintype "passive"))
      (node (ref "J2") (pin "5") (pinfunction "5_5") (pintype "passive"))
      (node (ref "J3") (pin "1") (pinfunction "1_1") (pintype "passive"))
      (node (ref "R1") (pin "2") (pinfunction "2_2") (pintype "passive"))
      (node (ref "R2") (pin "2") (pinfunction "2_2") (pintype "passive"))
      (node (ref "R22") (pin "2") (pinfunction "2_2") (pintype "passive"))
    )
    (net (code "63") (name "VCC_MSP") (class "Default")
      (node (ref "C3") (pin "1") (pinfunction "1_1") (pintype "passive"))
      (node (ref "C6") (pin "1") (pinfunction "1_1") (pintype "passive"))
      (node (ref "J3") (pin "2") (pinfunction "2_2") (pintype "passive"))
      (node (ref "J7") (pin "2") (pinfunction "2_2") (pintype "passive"))
      (node (ref "R5") (pin "2") (pinfunction "2_2") (pintype "passive"))
      (node (ref "U1") (pin "32") (pinfunction "DVCC_32") (pintype "power_in"))
    )
    (net (code "64") (name "VREG") (class "Default")
      (node (ref "C4") (pin "1") (pinfunction "1_1") (pintype "passive"))
      (node (ref "U1") (pin "20") (pinfunction "VREG_20") (pintype "power_in"))
    )
    (net (code "65") (name "unconnected-(J1-Pad2)") (class "Default")
      (node (ref "J1") (pin "2") (pinfunction "2_2") (pintype "passive"))
    )
    (net (code "66") (name "unconnected-(J1-Pad6)") (class "Default")
      (node (ref "J1") (pin "6") (pinfunction "6_6") (pintype "passive"))
    )
    (net (code "67") (name "unconnected-(J1-Pad7)") (class "Default")
      (node (ref "J1") (pin "7") (pinfunction "7_7") (pintype "passive"))
    )
    (net (code "68") (name "unconnected-(J1-Pad14)") (class "Default")
      (node (ref "J1") (pin "14") (pinfunction "14_14") (pintype "passive"))
    )
    (net (code "69") (name "unconnected-(J1-Pad15)") (class "Default")
      (node (ref "J1") (pin "15") (pinfunction "15_15") (pintype "passive"))
    )
    (net (code "70") (name "unconnected-(J1-Pad16)") (class "Default")
      (node (ref "J1") (pin "16") (pinfunction "16_16") (pintype "passive"))
    )
    (net (code "71") (name "unconnected-(J1-Pad17)") (class "Default")
      (node (ref "J1") (pin "17") (pinfunction "17_17") (pintype "passive"))
    )
    (net (code "72") (name "unconnected-(J1-Pad18)") (class "Default")
      (node (ref "J1") (pin "18") (pinfunction "18_18") (pintype "passive"))
    )
    (net (code "73") (name "unconnected-(J1-Pad19)") (class "Default")
      (node (ref "J1") (pin "19") (pinfunction "19_19") (pintype "passive"))
    )
    (net (code "74") (name "unconnected-(J1-Pad23)") (class "Default")
      (node (ref "J1") (pin "23") (pinfunction "23_23") (pintype "passive"))
    )
    (net (code "75") (name "unconnected-(J1-Pad24)") (class "Default")
      (node (ref "J1") (pin "24") (pinfunction "24_24") (pintype "passive"))
    )
    (net (code "76") (name "unconnected-(J1-Pad25)") (class "Default")
      (node (ref "J1") (pin "25") (pinfunction "25_25") (pintype "passive"))
    )
    (net (code "77") (name "unconnected-(J1-Pad26)") (class "Default")
      (node (ref "J1") (pin "26") (pinfunction "26_26") (pintype "passive"))
    )
    (net (code "78") (name "unconnected-(J1-Pad27)") (class "Default")
      (node (ref "J1") (pin "27") (pinfunction "27_27") (pintype "passive"))
    )
    (net (code "79") (name "unconnected-(J1-Pad28)") (class "Default")
      (node (ref "J1") (pin "28") (pinfunction "28_28") (pintype "passive"))
    )
    (net (code "80") (name "unconnected-(J1-Pad29)") (class "Default")
      (node (ref "J1") (pin "29") (pinfunction "29_29") (pintype "passive"))
    )
    (net (code "81") (name "unconnected-(J1-Pad30)") (class "Default")
      (node (ref "J1") (pin "30") (pinfunction "30_30") (pintype "passive"))
    )
    (net (code "82") (name "unconnected-(J1-Pad31)") (class "Default")
      (node (ref "J1") (pin "31") (pinfunction "31_31") (pintype "passive"))
    )
    (net (code "83") (name "unconnected-(J1-Pad32)") (class "Default")
      (node (ref "J1") (pin "32") (pinfunction "32_32") (pintype "passive"))
    )
    (net (code "84") (name "unconnected-(J1-Pad33)") (class "Default")
      (node (ref "J1") (pin "33") (pinfunction "33_33") (pintype "passive"))
    )
    (net (code "85") (name "unconnected-(J1-Pad34)") (class "Default")
      (node (ref "J1") (pin "34") (pinfunction "34_34") (pintype "passive"))
    )
    (net (code "86") (name "unconnected-(J1-Pad35)") (class "Default")
      (node (ref "J1") (pin "35") (pinfunction "35_35") (pintype "passive"))
    )
    (net (code "87") (name "unconnected-(J1-Pad36)") (class "Default")
      (node (ref "J1") (pin "36") (pinfunction "36_36") (pintype "passive"))
    )
    (net (code "88") (name "unconnected-(J1-Pad37)") (class "Default")
      (node (ref "J1") (pin "37") (pinfunction "37_37") (pintype "passive"))
    )
    (net (code "89") (name "unconnected-(J1-Pad38)") (class "Default")
      (node (ref "J1") (pin "38") (pinfunction "38_38") (pintype "passive"))
    )
    (net (code "90") (name "unconnected-(J1-Pad39)") (class "Default")
      (node (ref "J1") (pin "39") (pinfunction "39_39") (pintype "passive"))
    )
    (net (code "91") (name "unconnected-(J1-Pad40)") (class "Default")
      (node (ref "J1") (pin "40") (pinfunction "40_40") (pintype "passive"))
    )
    (net (code "92") (name "unconnected-(J10-L_HOLE-PadH1)") (class "Default")
      (node (ref "J10") (pin "H1") (pinfunction "L_HOLE_H1") (pintype "passive"))
    )
    (net (code "93") (name "unconnected-(J10-PadB2)") (class "Default")
      (node (ref "J10") (pin "B2") (pinfunction "B2_B2") (pintype "passive"))
    )
    (net (code "94") (name "unconnected-(J10-R_HOLE-PadH2)") (class "Default")
      (node (ref "J10") (pin "H2") (pinfunction "R_HOLE_H2") (pintype "passive"))
    )
  )
)
